# right_thumb.net
KiCad netlist of a schematic drawn in EAGLE
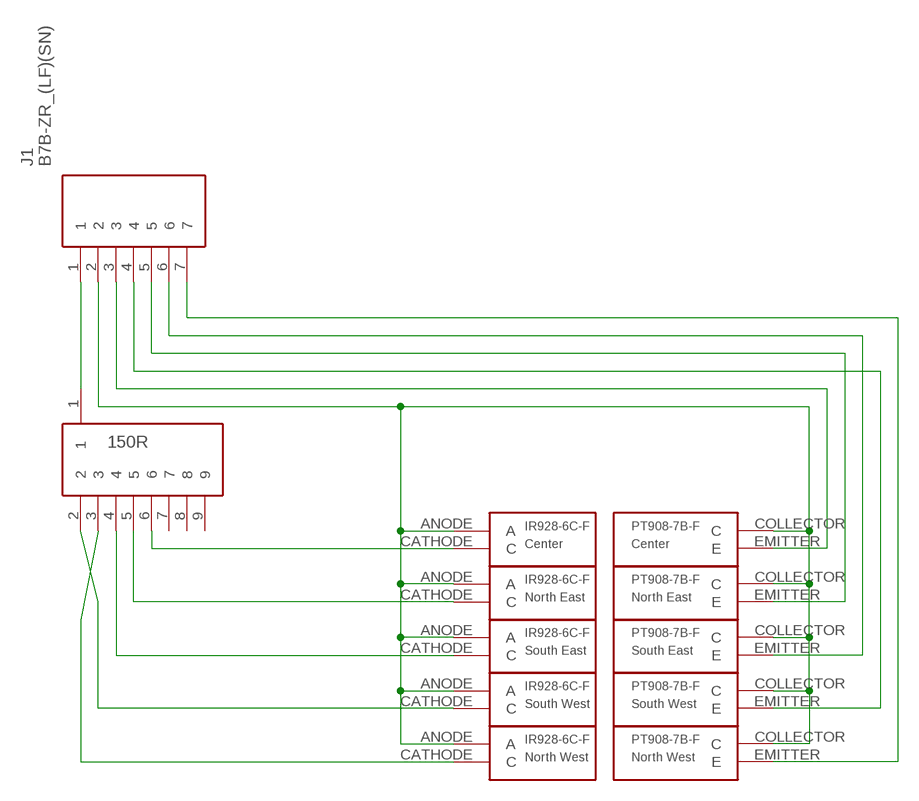
[diagram p0: schematic, sheet 1]

(export (version "E")
  (design (tool "Eeschema 10.0.6"))
  (components
    (comp (ref "J1")
      (value "B7B-ZR_(LF)(SN)")
      (footprint "eagle-import:SHDR7W50P0X150_1X7_1200X350X45")
      (fields
        (field (name "MANUFACTURER_PART_NUMBER") "B7B-ZR (LF)(SN)")
        (field (name "RS_PART_NUMBER") "7620828")
      )
      (libsource (lib "eagle-import") (part "B7B-ZR_(LF)(SN)"))
    )
    (comp (ref "LED1")
      (value "Center")
      (footprint "eagle-import:IR928-6C-F")
      (libsource (lib "eagle-import") (part "IR928-6C-F"))
    )
    (comp (ref "LED2")
      (value "North East")
      (footprint "eagle-import:IR928-6C-F")
      (libsource (lib "eagle-import") (part "IR928-6C-F"))
    )
    (comp (ref "LED3")
      (value "South East")
      (footprint "eagle-import:IR928-6C-F")
      (libsource (lib "eagle-import") (part "IR928-6C-F"))
    )
    (comp (ref "LED4")
      (value "South West")
      (footprint "eagle-import:IR928-6C-F")
      (libsource (lib "eagle-import") (part "IR928-6C-F"))
    )
    (comp (ref "LED5")
      (value "North West")
      (footprint "eagle-import:IR928-6C-F")
      (libsource (lib "eagle-import") (part "IR928-6C-F"))
    )
    (comp (ref "PT1")
      (value "Center")
      (footprint "eagle-import:PT908-7B-F")
      (libsource (lib "eagle-import") (part "PT908-7B-F"))
    )
    (comp (ref "PT2")
      (value "North East")
      (footprint "eagle-import:PT908-7B-F")
      (libsource (lib "eagle-import") (part "PT908-7B-F"))
    )
    (comp (ref "PT3")
      (value "South East")
      (footprint "eagle-import:PT908-7B-F")
      (libsource (lib "eagle-import") (part "PT908-7B-F"))
    )
    (comp (ref "PT4")
      (value "South West")
      (footprint "eagle-import:PT908-7B-F")
      (libsource (lib "eagle-import") (part "PT908-7B-F"))
    )
    (comp (ref "PT5")
      (value "North West")
      (footprint "eagle-import:PT908-7B-F")
      (libsource (lib "eagle-import") (part "PT908-7B-F"))
    )
    (comp (ref "RN1")
      (value "150R")
      (footprint "eagle-import:9PIN-RESISTOR-NETWORK")
      (libsource (lib "eagle-import") (part "9PIN-RESISTOR-NETWORK9PIN-RESISTOR-NETWORK"))
    )
  )
  (nets
    (net (code "1") (name "Net-(J1-Pad1)") (class "Default")
      (node (ref "J1") (pin "1") (pinfunction "1_1") (pintype "bidirectional"))
      (node (ref "RN1") (pin "1") (pinfunction "1_1") (pintype "bidirectional"))
    )
    (net (code "2") (name "Net-(LED1-A)") (class "Default")
      (node (ref "J1") (pin "2") (pinfunction "2_2") (pintype "bidirectional"))
      (node (ref "LED1") (pin "ANODE") (pinfunction "A_ANODE") (pintype "input"))
      (node (ref "LED2") (pin "ANODE") (pinfunction "A_ANODE") (pintype "input"))
      (node (ref "LED3") (pin "ANODE") (pinfunction "A_ANODE") (pintype "input"))
      (node (ref "LED4") (pin "ANODE") (pinfunction "A_ANODE") (pintype "input"))
      (node (ref "LED5") (pin "ANODE") (pinfunction "A_ANODE") (pintype "input"))
      (node (ref "PT1") (pin "COLLECTOR") (pinfunction "C_COLLECTOR") (pintype "input"))
      (node (ref "PT2") (pin "COLLECTOR") (pinfunction "C_COLLECTOR") (pintype "input"))
      (node (ref "PT3") (pin "COLLECTOR") (pinfunction "C_COLLECTOR") (pintype "input"))
      (node (ref "PT4") (pin "COLLECTOR") (pinfunction "C_COLLECTOR") (pintype "input"))
      (node (ref "PT5") (pin "COLLECTOR") (pinfunction "C_COLLECTOR") (pintype "input"))
    )
    (net (code "3") (name "Net-(LED1-C)") (class "Default")
      (node (ref "LED1") (pin "CATHODE") (pinfunction "C_CATHODE") (pintype "output"))
      (node (ref "RN1") (pin "6") (pinfunction "6_6") (pintype "bidirectional"))
    )
    (net (code "4") (name "Net-(LED2-C)") (class "Default")
      (node (ref "LED2") (pin "CATHODE") (pinfunction "C_CATHODE") (pintype "output"))
      (node (ref "RN1") (pin "5") (pinfunction "5_5") (pintype "bidirectional"))
    )
    (net (code "5") (name "Net-(LED3-C)") (class "Default")
      (node (ref "LED3") (pin "CATHODE") (pinfunction "C_CATHODE") (pintype "output"))
      (node (ref "RN1") (pin "4") (pinfunction "4_4") (pintype "bidirectional"))
    )
    (net (code "6") (name "Net-(LED4-C)") (class "Default")
      (node (ref "LED4") (pin "CATHODE") (pinfunction "C_CATHODE") (pintype "output"))
      (node (ref "RN1") (pin "2") (pinfunction "2_2") (pintype "bidirectional"))
    )
    (net (code "7") (name "Net-(LED5-C)") (class "Default")
      (node (ref "LED5") (pin "CATHODE") (pinfunction "C_CATHODE") (pintype "output"))
      (node (ref "RN1") (pin "3") (pinfunction "3_3") (pintype "bidirectional"))
    )
    (net (code "8") (name "Net-(PT1-E)") (class "Default")
      (node (ref "J1") (pin "3") (pinfunction "3_3") (pintype "bidirectional"))
      (node (ref "PT1") (pin "EMITTER") (pinfunction "E_EMITTER") (pintype "output"))
    )
    (net (code "9") (name "Net-(PT2-E)") (class "Default")
      (node (ref "J1") (pin "5") (pinfunction "5_5") (pintype "bidirectional"))
      (node (ref "PT2") (pin "EMITTER") (pinfunction "E_EMITTER") (pintype "output"))
    )
    (net (code "10") (name "Net-(PT3-E)") (class "Default")
      (node (ref "J1") (pin "6") (pinfunction "6_6") (pintype "bidirectional"))
      (node (ref "PT3") (pin "EMITTER") (pinfunction "E_EMITTER") (pintype "output"))
    )
    (net (code "11") (name "Net-(PT4-E)") (class "Default")
      (node (ref "J1") (pin "4") (pinfunction "4_4") (pintype "bidirectional"))
      (node (ref "PT4") (pin "EMITTER") (pinfunction "E_EMITTER") (pintype "output"))
    )
    (net (code "12") (name "Net-(PT5-E)") (class "Default")
      (node (ref "J1") (pin "7") (pinfunction "7_7") (pintype "bidirectional"))
      (node (ref "PT5") (pin "EMITTER") (pinfunction "E_EMITTER") (pintype "output"))
    )
    (net (code "13") (name "unconnected-(RN1-Pad7)") (class "Default")
      (node (ref "RN1") (pin "7") (pinfunction "7_7") (pintype "bidirectional"))
    )
    (net (code "14") (name "unconnected-(RN1-Pad8)") (class "Default")
      (node (ref "RN1") (pin "8") (pinfunction "8_8") (pintype "bidirectional"))
    )
    (net (code "15") (name "unconnected-(RN1-Pad9)") (class "Default")
      (node (ref "RN1") (pin "9") (pinfunction "9_9") (pintype "bidirectional"))
    )
  )
)
